# ZynqEMIO_2.net
KiCad netlist of a schematic drawn in Altium Designer
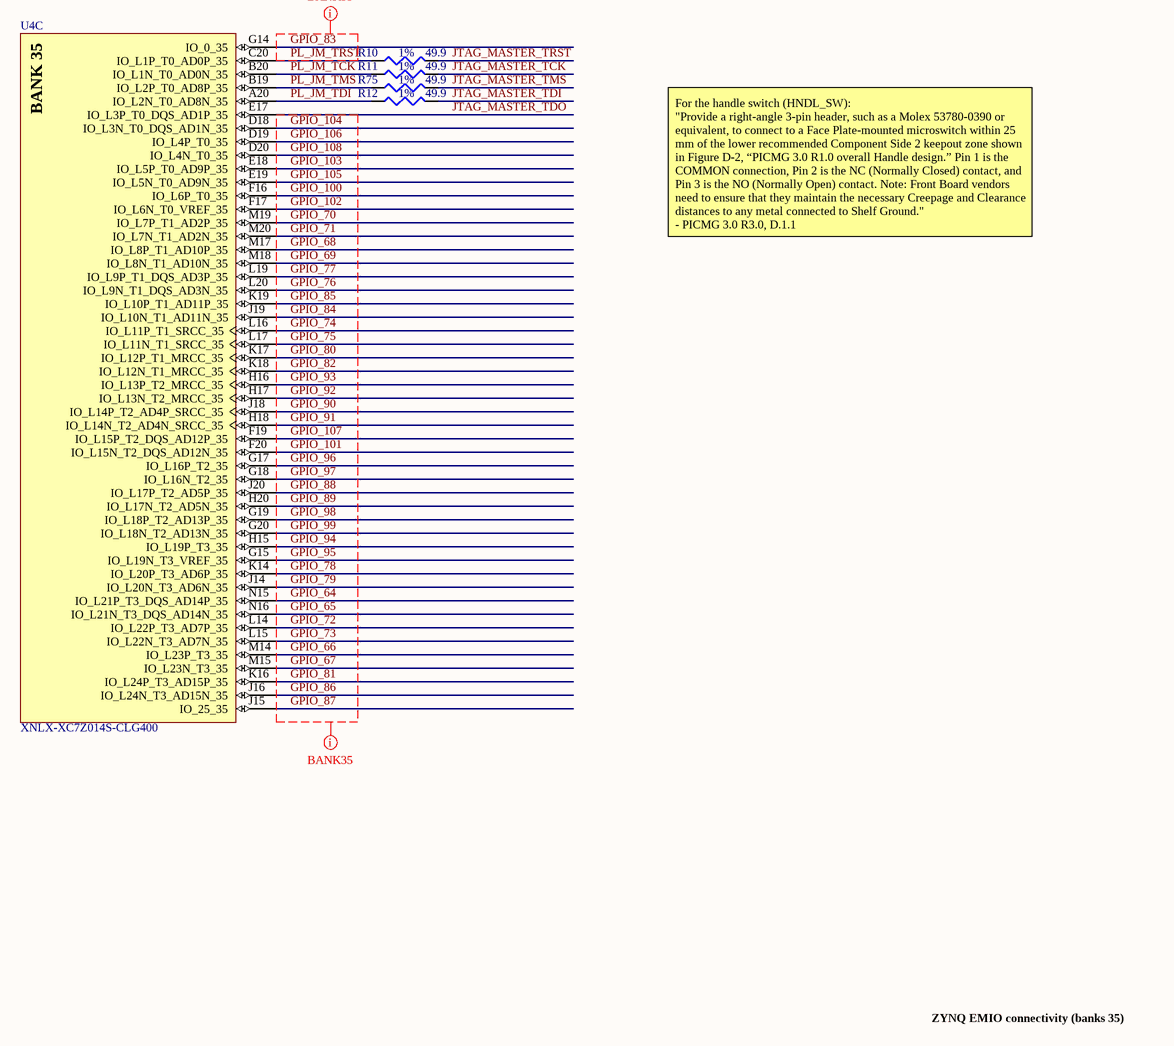
[diagram p0: ZynqEMIO_2.SchDoc]

(export (version "E")
  (design (tool "Eeschema 10.0.6"))
  (components
    (comp (ref "R10")
      (value "49.9")
      (footprint "R0402_IPC_H")
      (description "Resistor")
      (fields
        (field (name "TOLERANCE") "1%")
        (field (name "MANUFACTURER") "Panasonic")
        (field (name "PART") "ERJ-2RKF49R9X")
      )
      (libsource (lib "CustomParts") (part "Res"))
    )
    (comp (ref "R11")
      (value "49.9")
      (footprint "R0402_IPC_H")
      (description "Resistor")
      (fields
        (field (name "TOLERANCE") "1%")
        (field (name "MANUFACTURER") "Panasonic")
        (field (name "PART") "ERJ-2RKF49R9X")
      )
      (libsource (lib "CustomParts") (part "Res"))
    )
    (comp (ref "R12")
      (value "49.9")
      (footprint "R0402_IPC_H")
      (description "Resistor")
      (fields
        (field (name "TOLERANCE") "1%")
        (field (name "MANUFACTURER") "Panasonic")
        (field (name "PART") "ERJ-2RKF49R9X")
      )
      (libsource (lib "CustomParts") (part "Res"))
    )
    (comp (ref "R75")
      (value "49.9")
      (footprint "R0402_IPC_H")
      (description "Resistor")
      (fields
        (field (name "TOLERANCE") "1%")
        (field (name "MANUFACTURER") "Panasonic")
        (field (name "PART") "ERJ-2RKF49R9X")
      )
      (libsource (lib "CustomParts") (part "Res"))
    )
    (comp (ref "U4")
      (value "XNLX-XC7Z014S-CLG400")
      (footprint "CLG400")
      (fields (field (name "MANUFACTURER") "Xilinx") (field (name "PART") "XC7Z014S-1CLG400C"))
      (libsource (lib "CustomParts") (part "XNLX-XC7Z020-CLG400"))
    )
  )
  (nets
    (net (code "1") (name "/GPIO_64") (class "Default")
      (node (ref "U4") (pin "N15") (pinfunction "IO_L21P_T3_DQS_AD14P_35_N15") (pintype "bidirectional"))
    )
    (net (code "2") (name "/GPIO_65") (class "Default")
      (node (ref "U4") (pin "N16") (pinfunction "IO_L21N_T3_DQS_AD14N_35_N16") (pintype "bidirectional"))
    )
    (net (code "3") (name "/GPIO_66") (class "Default")
      (node (ref "U4") (pin "M14") (pinfunction "IO_L23P_T3_35_M14") (pintype "bidirectional"))
    )
    (net (code "4") (name "/GPIO_67") (class "Default")
      (node (ref "U4") (pin "M15") (pinfunction "IO_L23N_T3_35_M15") (pintype "bidirectional"))
    )
    (net (code "5") (name "/GPIO_68") (class "Default")
      (node (ref "U4") (pin "M17") (pinfunction "IO_L8P_T1_AD10P_35_M17") (pintype "bidirectional"))
    )
    (net (code "6") (name "/GPIO_69") (class "Default")
      (node (ref "U4") (pin "M18") (pinfunction "IO_L8N_T1_AD10N_35_M18") (pintype "bidirectional"))
    )
    (net (code "7") (name "/GPIO_70") (class "Default")
      (node (ref "U4") (pin "M19") (pinfunction "IO_L7P_T1_AD2P_35_M19") (pintype "bidirectional"))
    )
    (net (code "8") (name "/GPIO_71") (class "Default")
      (node (ref "U4") (pin "M20") (pinfunction "IO_L7N_T1_AD2N_35_M20") (pintype "bidirectional"))
    )
    (net (code "9") (name "/GPIO_72") (class "Default")
      (node (ref "U4") (pin "L14") (pinfunction "IO_L22P_T3_AD7P_35_L14") (pintype "bidirectional"))
    )
    (net (code "10") (name "/GPIO_73") (class "Default")
      (node (ref "U4") (pin "L15") (pinfunction "IO_L22N_T3_AD7N_35_L15") (pintype "bidirectional"))
    )
    (net (code "11") (name "/GPIO_74") (class "Default")
      (node (ref "U4") (pin "L16") (pinfunction "IO_L11P_T1_SRCC_35_L16") (pintype "bidirectional"))
    )
    (net (code "12") (name "/GPIO_75") (class "Default")
      (node (ref "U4") (pin "L17") (pinfunction "IO_L11N_T1_SRCC_35_L17") (pintype "bidirectional"))
    )
    (net (code "13") (name "/GPIO_76") (class "Default")
      (node (ref "U4") (pin "L20") (pinfunction "IO_L9N_T1_DQS_AD3N_35_L20") (pintype "bidirectional"))
    )
    (net (code "14") (name "/GPIO_77") (class "Default")
      (node (ref "U4") (pin "L19") (pinfunction "IO_L9P_T1_DQS_AD3P_35_L19") (pintype "bidirectional"))
    )
    (net (code "15") (name "/GPIO_78") (class "Default")
      (node (ref "U4") (pin "K14") (pinfunction "IO_L20P_T3_AD6P_35_K14") (pintype "bidirectional"))
    )
    (net (code "16") (name "/GPIO_79") (class "Default")
      (node (ref "U4") (pin "J14") (pinfunction "IO_L20N_T3_AD6N_35_J14") (pintype "bidirectional"))
    )
    (net (code "17") (name "/GPIO_80") (class "Default")
      (node (ref "U4") (pin "K17") (pinfunction "IO_L12P_T1_MRCC_35_K17") (pintype "bidirectional"))
    )
    (net (code "18") (name "/GPIO_81") (class "Default")
      (node (ref "U4") (pin "K16") (pinfunction "IO_L24P_T3_AD15P_35_K16") (pintype "bidirectional"))
    )
    (net (code "19") (name "/GPIO_82") (class "Default")
      (node (ref "U4") (pin "K18") (pinfunction "IO_L12N_T1_MRCC_35_K18") (pintype "bidirectional"))
    )
    (net (code "20") (name "/GPIO_83") (class "Default")
      (node (ref "U4") (pin "G14") (pinfunction "IO_0_35_G14") (pintype "bidirectional"))
    )
    (net (code "21") (name "/GPIO_84") (class "Default")
      (node (ref "U4") (pin "J19") (pinfunction "IO_L10N_T1_AD11N_35_J19") (pintype "bidirectional"))
    )
    (net (code "22") (name "/GPIO_85") (class "Default")
      (node (ref "U4") (pin "K19") (pinfunction "IO_L10P_T1_AD11P_35_K19") (pintype "bidirectional"))
    )
    (net (code "23") (name "/GPIO_86") (class "Default")
      (node (ref "U4") (pin "J16") (pinfunction "IO_L24N_T3_AD15N_35_J16") (pintype "bidirectional"))
    )
    (net (code "24") (name "/GPIO_87") (class "Default")
      (node (ref "U4") (pin "J15") (pinfunction "IO_25_35_J15") (pintype "bidirectional"))
    )
    (net (code "25") (name "/GPIO_88") (class "Default")
      (node (ref "U4") (pin "J20") (pinfunction "IO_L17P_T2_AD5P_35_J20") (pintype "bidirectional"))
    )
    (net (code "26") (name "/GPIO_89") (class "Default")
      (node (ref "U4") (pin "H20") (pinfunction "IO_L17N_T2_AD5N_35_H20") (pintype "bidirectional"))
    )
    (net (code "27") (name "/GPIO_90") (class "Default")
      (node (ref "U4") (pin "J18") (pinfunction "IO_L14P_T2_AD4P_SRCC_35_J18") (pintype "bidirectional"))
    )
    (net (code "28") (name "/GPIO_91") (class "Default")
      (node (ref "U4") (pin "H18") (pinfunction "IO_L14N_T2_AD4N_SRCC_35_H18") (pintype "bidirectional"))
    )
    (net (code "29") (name "/GPIO_92") (class "Default")
      (node (ref "U4") (pin "H17") (pinfunction "IO_L13N_T2_MRCC_35_H17") (pintype "bidirectional"))
    )
    (net (code "30") (name "/GPIO_93") (class "Default")
      (node (ref "U4") (pin "H16") (pinfunction "IO_L13P_T2_MRCC_35_H16") (pintype "bidirectional"))
    )
    (net (code "31") (name "/GPIO_94") (class "Default")
      (node (ref "U4") (pin "H15") (pinfunction "IO_L19P_T3_35_H15") (pintype "bidirectional"))
    )
    (net (code "32") (name "/GPIO_95") (class "Default")
      (node (ref "U4") (pin "G15") (pinfunction "IO_L19N_T3_VREF_35_G15") (pintype "bidirectional"))
    )
    (net (code "33") (name "/GPIO_96") (class "Default")
      (node (ref "U4") (pin "G17") (pinfunction "IO_L16P_T2_35_G17") (pintype "bidirectional"))
    )
    (net (code "34") (name "/GPIO_97") (class "Default")
      (node (ref "U4") (pin "G18") (pinfunction "IO_L16N_T2_35_G18") (pintype "bidirectional"))
    )
    (net (code "35") (name "/GPIO_98") (class "Default")
      (node (ref "U4") (pin "G19") (pinfunction "IO_L18P_T2_AD13P_35_G19") (pintype "bidirectional"))
    )
    (net (code "36") (name "/GPIO_99") (class "Default")
      (node (ref "U4") (pin "G20") (pinfunction "IO_L18N_T2_AD13N_35_G20") (pintype "bidirectional"))
    )
    (net (code "37") (name "/GPIO_100") (class "Default")
      (node (ref "U4") (pin "F16") (pinfunction "IO_L6P_T0_35_F16") (pintype "bidirectional"))
    )
    (net (code "38") (name "/GPIO_101") (class "Default")
      (node (ref "U4") (pin "F20") (pinfunction "IO_L15N_T2_DQS_AD12N_35_F20") (pintype "bidirectional"))
    )
    (net (code "39") (name "/GPIO_102") (class "Default")
      (node (ref "U4") (pin "F17") (pinfunction "IO_L6N_T0_VREF_35_F17") (pintype "bidirectional"))
    )
    (net (code "40") (name "/GPIO_103") (class "Default")
      (node (ref "U4") (pin "E18") (pinfunction "IO_L5P_T0_AD9P_35_E18") (pintype "bidirectional"))
    )
    (net (code "41") (name "/GPIO_104") (class "Default")
      (node (ref "U4") (pin "D18") (pinfunction "IO_L3N_T0_DQS_AD1N_35_D18") (pintype "bidirectional"))
    )
    (net (code "42") (name "/GPIO_105") (class "Default")
      (node (ref "U4") (pin "E19") (pinfunction "IO_L5N_T0_AD9N_35_E19") (pintype "bidirectional"))
    )
    (net (code "43") (name "/GPIO_106") (class "Default")
      (node (ref "U4") (pin "D19") (pinfunction "IO_L4P_T0_35_D19") (pintype "bidirectional"))
    )
    (net (code "44") (name "/GPIO_107") (class "Default")
      (node (ref "U4") (pin "F19") (pinfunction "IO_L15P_T2_DQS_AD12P_35_F19") (pintype "bidirectional"))
    )
    (net (code "45") (name "/GPIO_108") (class "Default")
      (node (ref "U4") (pin "D20") (pinfunction "IO_L4N_T0_35_D20") (pintype "bidirectional"))
    )
    (net (code "46") (name "/JTAG_MASTER_TCK") (class "Default")
      (node (ref "R11") (pin "1") (pinfunction "1_1") (pintype "passive"))
    )
    (net (code "47") (name "/JTAG_MASTER_TDI") (class "Default")
      (node (ref "R12") (pin "1") (pinfunction "1_1") (pintype "passive"))
    )
    (net (code "48") (name "/JTAG_MASTER_TDO") (class "Default")
      (node (ref "U4") (pin "E17") (pinfunction "IO_L3P_T0_DQS_AD1P_35_E17") (pintype "bidirectional"))
    )
    (net (code "49") (name "/JTAG_MASTER_TMS") (class "Default")
      (node (ref "R75") (pin "1") (pinfunction "1_1") (pintype "passive"))
    )
    (net (code "50") (name "/JTAG_MASTER_TRST") (class "Default")
      (node (ref "R10") (pin "1") (pinfunction "1_1") (pintype "passive"))
    )
    (net (code "51") (name "/PL_JM_TCK") (class "Default")
      (node (ref "R11") (pin "2") (pinfunction "2_2") (pintype "passive"))
      (node (ref "U4") (pin "B20") (pinfunction "IO_L1N_T0_AD0N_35_B20") (pintype "bidirectional"))
    )
    (net (code "52") (name "/PL_JM_TDI") (class "Default")
      (node (ref "R12") (pin "2") (pinfunction "2_2") (pintype "passive"))
      (node (ref "U4") (pin "A20") (pinfunction "IO_L2N_T0_AD8N_35_A20") (pintype "bidirectional"))
    )
    (net (code "53") (name "/PL_JM_TMS") (class "Default")
      (node (ref "R75") (pin "2") (pinfunction "2_2") (pintype "passive"))
      (node (ref "U4") (pin "B19") (pinfunction "IO_L2P_T0_AD8P_35_B19") (pintype "bidirectional"))
    )
    (net (code "54") (name "/PL_JM_TRST") (class "Default")
      (node (ref "R10") (pin "2") (pinfunction "2_2") (pintype "passive"))
      (node (ref "U4") (pin "C20") (pinfunction "IO_L1P_T0_AD0P_35_C20") (pintype "bidirectional"))
    )
  )
)
